# schematics.net
KiCad netlist of a schematic drawn in EAGLE
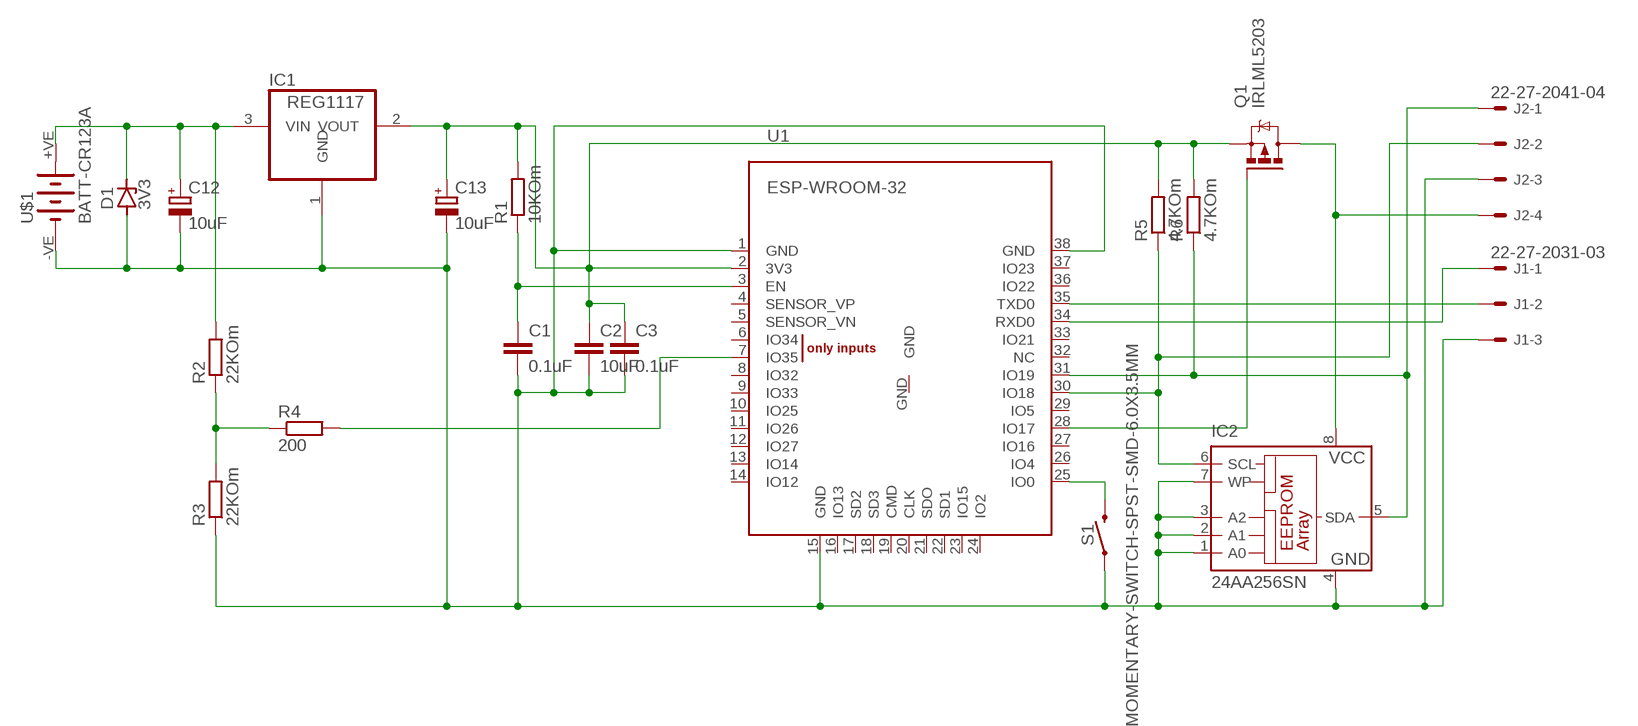
[diagram p0: schematic, sheet 1]

(export (version "E")
  (design (tool "Eeschema 10.0.6"))
  (components
    (comp (ref "C1")
      (value "0.1uF")
      (footprint "eagle-import:C1206K")
      (libsource (lib "eagle-import") (part "C-EUC1206K"))
    )
    (comp (ref "C2")
      (value "10uF")
      (footprint "eagle-import:C1206K")
      (libsource (lib "eagle-import") (part "C-EUC1206K"))
    )
    (comp (ref "C3")
      (value "0.1uF")
      (footprint "eagle-import:C1206K")
      (libsource (lib "eagle-import") (part "C-EUC1206K"))
    )
    (comp (ref "C12")
      (value "10uF")
      (footprint "eagle-import:SMC_E")
      (libsource (lib "eagle-import") (part "CPOL-EUSMCE"))
    )
    (comp (ref "C13")
      (value "10uF")
      (footprint "eagle-import:SMC_E")
      (libsource (lib "eagle-import") (part "CPOL-EUSMCE"))
    )
    (comp (ref "D1")
      (value "3V3")
      (footprint "eagle-import:SOT223")
      (libsource (lib "eagle-import") (part "ZENER-DIODESOT223"))
    )
    (comp (ref "IC1")
      (value "REG1117")
      (footprint "eagle-import:SOT223")
      (libsource (lib "eagle-import") (part "REG1117"))
    )
    (comp (ref "IC2")
      (value "24AA256SN")
      (footprint "eagle-import:SO-08")
      (fields (field (name "MPN") "24AA256T-I/SM"))
      (libsource (lib "eagle-import") (part "24SNAA256"))
    )
    (comp (ref "J1")
      (value "22-27-2031-03")
      (footprint "eagle-import:6410-03")
      (fields (field (name "MF") "MOLEX"))
      (libsource (lib "eagle-import") (part "22-?-0327-2031"))
    )
    (comp (ref "J2")
      (value "22-27-2041-04")
      (footprint "eagle-import:6410-04")
      (fields (field (name "MF") "MOLEX"))
      (libsource (lib "eagle-import") (part "22-?-0427-2041"))
    )
    (comp (ref "Q1")
      (value "IRLML5203")
      (footprint "eagle-import:MICRO3")
      (libsource (lib "eagle-import") (part "IRLML5203"))
    )
    (comp (ref "R1")
      (value "10KOm")
      (footprint "eagle-import:R1206")
      (libsource (lib "eagle-import") (part "R-EU_R1206"))
    )
    (comp (ref "R2")
      (value "22KOm")
      (footprint "eagle-import:R1206")
      (libsource (lib "eagle-import") (part "R-EU_R1206"))
    )
    (comp (ref "R3")
      (value "22KOm")
      (footprint "eagle-import:R1206")
      (libsource (lib "eagle-import") (part "R-EU_R1206"))
    )
    (comp (ref "R4")
      (value "200")
      (footprint "eagle-import:R1206")
      (libsource (lib "eagle-import") (part "R-EU_R1206"))
    )
    (comp (ref "R5")
      (value "4.7KOm")
      (footprint "eagle-import:R1206")
      (libsource (lib "eagle-import") (part "R-EU_R1206"))
    )
    (comp (ref "R6")
      (value "4.7KOm")
      (footprint "eagle-import:R1206")
      (libsource (lib "eagle-import") (part "R-EU_R1206"))
    )
    (comp (ref "S1")
      (value "MOMENTARY-SWITCH-SPST-SMD-6.0X3.5MM")
      (footprint "eagle-import:TACTILE_SWITCH_SMD_6.0X3.5MM")
      (libsource (lib "eagle-import") (part "MOMENTARY-SWITCH-SPST-SMD-6.0X3.5MM"))
    )
    (comp (ref "U$1")
      (value "BATT-CR123A")
      (footprint "eagle-import:KEYSTONE-2_3A")
      (libsource (lib "eagle-import") (part "BATT-CR123A"))
    )
    (comp (ref "U1")
      (value "ESP-WROOM-32")
      (footprint "eagle-import:ESP-WROOM-32")
      (libsource (lib "eagle-import") (part "ESP-WROOM-32"))
    )
  )
  (nets
    (net (code "1") (name "Net-(D1-A)") (class "Default")
      (node (ref "C1") (pin "2") (pinfunction "2_2") (pintype "passive"))
      (node (ref "C12") (pin "-") (pinfunction "-_-") (pintype "passive"))
      (node (ref "C13") (pin "-") (pinfunction "-_-") (pintype "passive"))
      (node (ref "C2") (pin "2") (pinfunction "2_2") (pintype "passive"))
      (node (ref "C3") (pin "2") (pinfunction "2_2") (pintype "passive"))
      (node (ref "D1") (pin "1") (pinfunction "A_1") (pintype "passive"))
      (node (ref "IC1") (pin "1") (pinfunction "GND_1") (pintype "power_in"))
      (node (ref "IC2") (pin "1") (pinfunction "A0_1") (pintype "input"))
      (node (ref "IC2") (pin "2") (pinfunction "A1_2") (pintype "input"))
      (node (ref "IC2") (pin "3") (pinfunction "A2_3") (pintype "input"))
      (node (ref "IC2") (pin "4") (pinfunction "GND_4") (pintype "power_in"))
      (node (ref "IC2") (pin "7") (pinfunction "WP_7") (pintype "input"))
      (node (ref "J1") (pin "3") (pinfunction "S_3") (pintype "passive"))
      (node (ref "J2") (pin "3") (pinfunction "S_3") (pintype "passive"))
      (node (ref "R3") (pin "1") (pinfunction "1_1") (pintype "passive"))
      (node (ref "S1") (pin "1") (pinfunction "1_1") (pintype "passive"))
      (node (ref "U$1") (pin "-VE") (pinfunction "-_-VE") (pintype "passive"))
      (node (ref "U1") (pin "1") (pinfunction "GND_1") (pintype "bidirectional"))
      (node (ref "U1") (pin "15") (pinfunction "GND_15") (pintype "bidirectional"))
      (node (ref "U1") (pin "38") (pinfunction "GND_38") (pintype "bidirectional"))
    )
    (net (code "2") (name "Net-(D1-C)") (class "Default")
      (node (ref "C12") (pin "+") (pinfunction "+_+") (pintype "passive"))
      (node (ref "D1") (pin "4") (pinfunction "C_4") (pintype "passive"))
      (node (ref "IC1") (pin "3") (pinfunction "VIN_3") (pintype "input"))
      (node (ref "R2") (pin "2") (pinfunction "2_2") (pintype "passive"))
      (node (ref "U$1") (pin "+VE") (pinfunction "+_+VE") (pintype "passive"))
    )
    (net (code "3") (name "Net-(IC1-VOUT)") (class "Default")
      (node (ref "C13") (pin "+") (pinfunction "+_+") (pintype "passive"))
      (node (ref "C2") (pin "1") (pinfunction "1_1") (pintype "passive"))
      (node (ref "C3") (pin "1") (pinfunction "1_1") (pintype "passive"))
      (node (ref "IC1") (pin "2") (pinfunction "VOUT_2") (pintype "output"))
      (node (ref "Q1") (pin "2") (pinfunction "S_2") (pintype "passive"))
      (node (ref "R1") (pin "2") (pinfunction "2_2") (pintype "passive"))
      (node (ref "R5") (pin "2") (pinfunction "2_2") (pintype "passive"))
      (node (ref "R6") (pin "2") (pinfunction "2_2") (pintype "passive"))
      (node (ref "U1") (pin "2") (pinfunction "3V3_2") (pintype "bidirectional"))
    )
    (net (code "4") (name "Net-(IC2-SCL)") (class "Default")
      (node (ref "IC2") (pin "6") (pinfunction "SCL_6") (pintype "input"))
      (node (ref "J2") (pin "2") (pinfunction "S_2") (pintype "passive"))
      (node (ref "R5") (pin "1") (pinfunction "1_1") (pintype "passive"))
      (node (ref "U1") (pin "30") (pinfunction "IO18_30") (pintype "bidirectional"))
    )
    (net (code "5") (name "Net-(IC2-SDA)") (class "Default")
      (node (ref "IC2") (pin "5") (pinfunction "SDA_5") (pintype "bidirectional"))
      (node (ref "J2") (pin "1") (pinfunction "S_1") (pintype "passive"))
      (node (ref "R6") (pin "1") (pinfunction "1_1") (pintype "passive"))
      (node (ref "U1") (pin "31") (pinfunction "IO19_31") (pintype "bidirectional"))
    )
    (net (code "6") (name "Net-(IC2-VCC)") (class "Default")
      (node (ref "IC2") (pin "8") (pinfunction "VCC_8") (pintype "power_in"))
      (node (ref "J2") (pin "4") (pinfunction "S_4") (pintype "passive"))
      (node (ref "Q1") (pin "3") (pinfunction "D_3") (pintype "passive"))
    )
    (net (code "7") (name "Net-(J1A-S)") (class "Default")
      (node (ref "J1") (pin "1") (pinfunction "S_1") (pintype "passive"))
      (node (ref "U1") (pin "34") (pinfunction "RXD0_34") (pintype "bidirectional"))
    )
    (net (code "8") (name "Net-(J1B-S)") (class "Default")
      (node (ref "J1") (pin "2") (pinfunction "S_2") (pintype "passive"))
      (node (ref "U1") (pin "35") (pinfunction "TXD0_35") (pintype "bidirectional"))
    )
    (net (code "9") (name "Net-(Q1-G)") (class "Default")
      (node (ref "Q1") (pin "1") (pinfunction "G_1") (pintype "passive"))
      (node (ref "U1") (pin "28") (pinfunction "IO17_28") (pintype "bidirectional"))
    )
    (net (code "10") (name "Net-(R2-Pad1)") (class "Default")
      (node (ref "R2") (pin "1") (pinfunction "1_1") (pintype "passive"))
      (node (ref "R3") (pin "2") (pinfunction "2_2") (pintype "passive"))
      (node (ref "R4") (pin "1") (pinfunction "1_1") (pintype "passive"))
    )
    (net (code "11") (name "Net-(U1-EN)") (class "Default")
      (node (ref "C1") (pin "1") (pinfunction "1_1") (pintype "passive"))
      (node (ref "R1") (pin "1") (pinfunction "1_1") (pintype "passive"))
      (node (ref "U1") (pin "3") (pinfunction "EN_3") (pintype "bidirectional"))
    )
    (net (code "12") (name "Net-(U1-IO0)") (class "Default")
      (node (ref "S1") (pin "2") (pinfunction "2_2") (pintype "passive"))
      (node (ref "U1") (pin "25") (pinfunction "IO0_25") (pintype "bidirectional"))
    )
    (net (code "13") (name "Net-(U1-IO35)") (class "Default")
      (node (ref "R4") (pin "2") (pinfunction "2_2") (pintype "passive"))
      (node (ref "U1") (pin "7") (pinfunction "IO35_7") (pintype "input"))
    )
    (net (code "14") (name "unconnected-(U1-CLK-Pad20)") (class "Default")
      (node (ref "U1") (pin "20") (pinfunction "CLK_20") (pintype "bidirectional"))
    )
    (net (code "15") (name "unconnected-(U1-CMD-Pad19)") (class "Default")
      (node (ref "U1") (pin "19") (pinfunction "CMD_19") (pintype "bidirectional"))
    )
    (net (code "16") (name "unconnected-(U1-IO2-Pad24)") (class "Default")
      (node (ref "U1") (pin "24") (pinfunction "IO2_24") (pintype "bidirectional"))
    )
    (net (code "17") (name "unconnected-(U1-IO4-Pad26)") (class "Default")
      (node (ref "U1") (pin "26") (pinfunction "IO4_26") (pintype "bidirectional"))
    )
    (net (code "18") (name "unconnected-(U1-IO5-Pad29)") (class "Default")
      (node (ref "U1") (pin "29") (pinfunction "IO5_29") (pintype "bidirectional"))
    )
    (net (code "19") (name "unconnected-(U1-IO12-Pad14)") (class "Default")
      (node (ref "U1") (pin "14") (pinfunction "IO12_14") (pintype "bidirectional"))
    )
    (net (code "20") (name "unconnected-(U1-IO13-Pad16)") (class "Default")
      (node (ref "U1") (pin "16") (pinfunction "IO13_16") (pintype "bidirectional"))
    )
    (net (code "21") (name "unconnected-(U1-IO14-Pad13)") (class "Default")
      (node (ref "U1") (pin "13") (pinfunction "IO14_13") (pintype "bidirectional"))
    )
    (net (code "22") (name "unconnected-(U1-IO15-Pad23)") (class "Default")
      (node (ref "U1") (pin "23") (pinfunction "IO15_23") (pintype "bidirectional"))
    )
    (net (code "23") (name "unconnected-(U1-IO16-Pad27)") (class "Default")
      (node (ref "U1") (pin "27") (pinfunction "IO16_27") (pintype "bidirectional"))
    )
    (net (code "24") (name "unconnected-(U1-IO21-Pad33)") (class "Default")
      (node (ref "U1") (pin "33") (pinfunction "IO21_33") (pintype "bidirectional"))
    )
    (net (code "25") (name "unconnected-(U1-IO22-Pad36)") (class "Default")
      (node (ref "U1") (pin "36") (pinfunction "IO22_36") (pintype "bidirectional"))
    )
    (net (code "26") (name "unconnected-(U1-IO23-Pad37)") (class "Default")
      (node (ref "U1") (pin "37") (pinfunction "IO23_37") (pintype "bidirectional"))
    )
    (net (code "27") (name "unconnected-(U1-IO25-Pad10)") (class "Default")
      (node (ref "U1") (pin "10") (pinfunction "IO25_10") (pintype "bidirectional"))
    )
    (net (code "28") (name "unconnected-(U1-IO26-Pad11)") (class "Default")
      (node (ref "U1") (pin "11") (pinfunction "IO26_11") (pintype "bidirectional"))
    )
    (net (code "29") (name "unconnected-(U1-IO27-Pad12)") (class "Default")
      (node (ref "U1") (pin "12") (pinfunction "IO27_12") (pintype "bidirectional"))
    )
    (net (code "30") (name "unconnected-(U1-IO32-Pad8)") (class "Default")
      (node (ref "U1") (pin "8") (pinfunction "IO32_8") (pintype "bidirectional"))
    )
    (net (code "31") (name "unconnected-(U1-IO33-Pad9)") (class "Default")
      (node (ref "U1") (pin "9") (pinfunction "IO33_9") (pintype "bidirectional"))
    )
    (net (code "32") (name "unconnected-(U1-IO34-Pad6)") (class "Default")
      (node (ref "U1") (pin "6") (pinfunction "IO34_6") (pintype "input"))
    )
    (net (code "33") (name "unconnected-(U1-NC-Pad32)") (class "Default")
      (node (ref "U1") (pin "32") (pinfunction "NC_32") (pintype "bidirectional"))
    )
    (net (code "34") (name "unconnected-(U1-PadGND)") (class "Default")
      (node (ref "U1") (pin "GND") (pinfunction "GND_GND") (pintype "bidirectional"))
    )
    (net (code "35") (name "unconnected-(U1-SD1-Pad22)") (class "Default")
      (node (ref "U1") (pin "22") (pinfunction "SD1_22") (pintype "bidirectional"))
    )
    (net (code "36") (name "unconnected-(U1-SD2-Pad17)") (class "Default")
      (node (ref "U1") (pin "17") (pinfunction "SD2_17") (pintype "bidirectional"))
    )
    (net (code "37") (name "unconnected-(U1-SD3-Pad18)") (class "Default")
      (node (ref "U1") (pin "18") (pinfunction "SD3_18") (pintype "bidirectional"))
    )
    (net (code "38") (name "unconnected-(U1-SDO-Pad21)") (class "Default")
      (node (ref "U1") (pin "21") (pinfunction "SDO_21") (pintype "bidirectional"))
    )
    (net (code "39") (name "unconnected-(U1-SENSOR_VN-Pad5)") (class "Default")
      (node (ref "U1") (pin "5") (pinfunction "SENSOR_VN_5") (pintype "input"))
    )
    (net (code "40") (name "unconnected-(U1-SENSOR_VP-Pad4)") (class "Default")
      (node (ref "U1") (pin "4") (pinfunction "SENSOR_VP_4") (pintype "input"))
    )
  )
)
